# core.net
KiCad netlist of a schematic drawn in Altium Designer
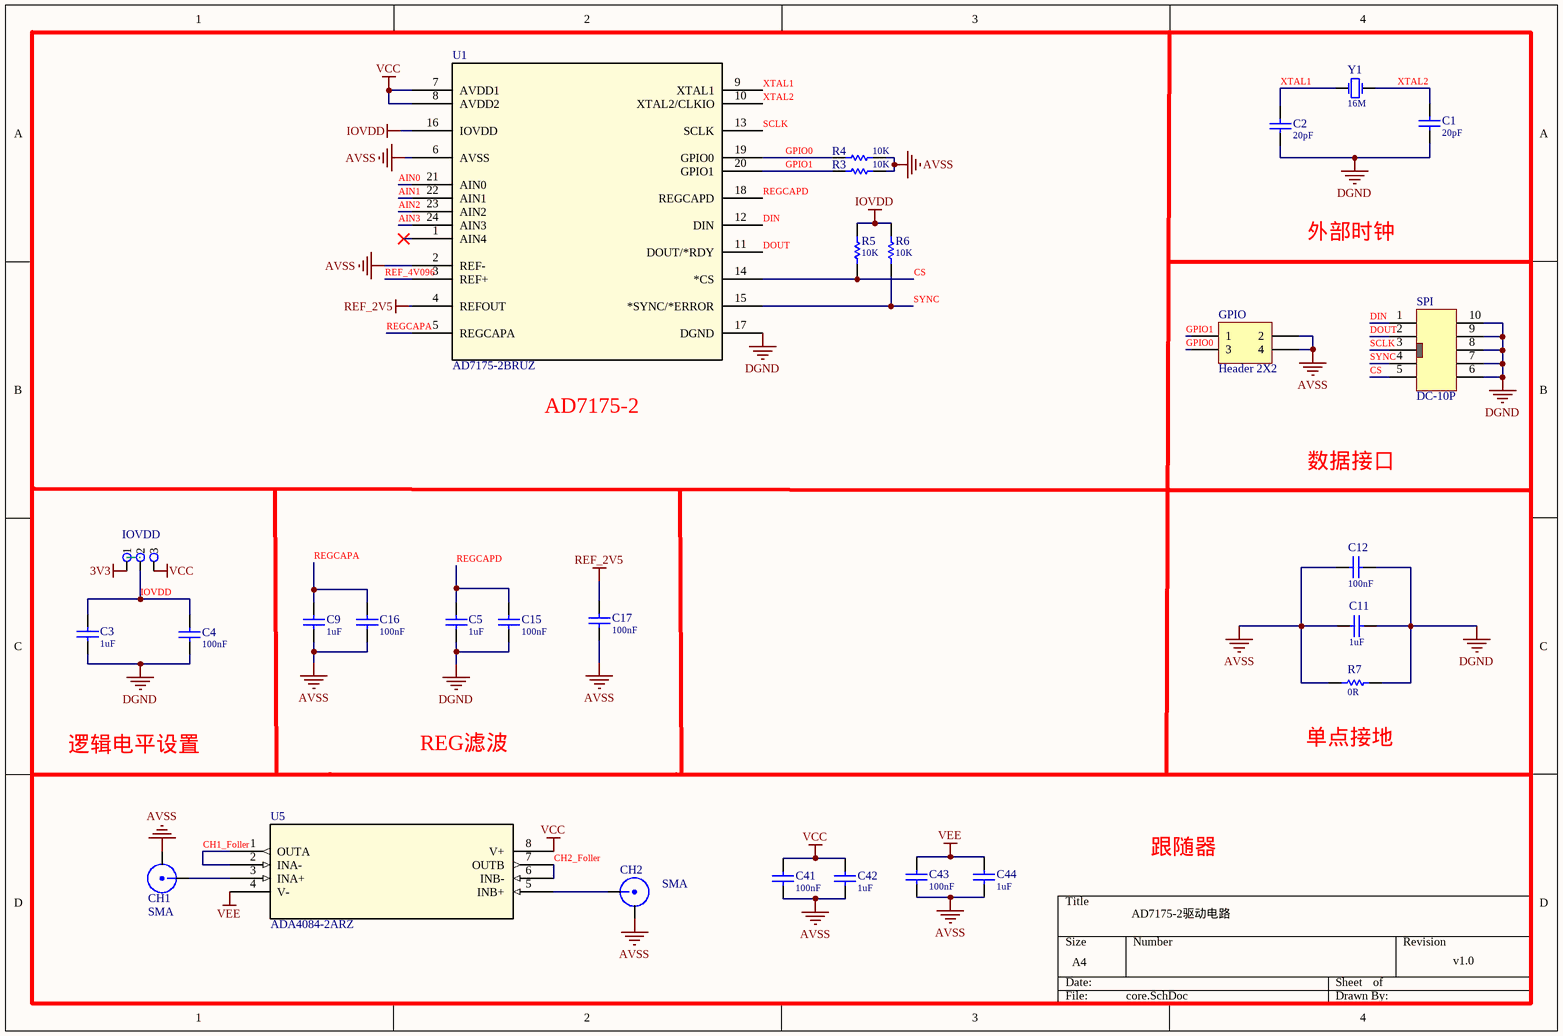
[diagram p0: core.SchDoc]

(export (version "E")
  (design (tool "Eeschema 10.0.6"))
  (components
    (comp (ref "C1")
      (value "20pF")
      (footprint "C0603-L")
      (description "贴片瓷片电容")
      (fields (field (name "Comment") "Cap-S"))
      (libsource (lib "XuZhe") (part "Cap-S"))
    )
    (comp (ref "C2")
      (value "20pF")
      (footprint "C0603-L")
      (description "贴片瓷片电容")
      (fields (field (name "Comment") "Cap-S"))
      (libsource (lib "XuZhe") (part "Cap-S"))
    )
    (comp (ref "C3")
      (value "1uF")
      (footprint "C0603-L")
      (description "贴片瓷片电容")
      (fields (field (name "Comment") "Cap-S"))
      (libsource (lib "XuZhe") (part "Cap-S"))
    )
    (comp (ref "C4")
      (value "100nF")
      (footprint "C0603-L")
      (description "贴片瓷片电容")
      (fields (field (name "Comment") "Cap-S"))
      (libsource (lib "XuZhe") (part "Cap-S"))
    )
    (comp (ref "C5")
      (value "1uF")
      (footprint "C0603-L")
      (description "贴片瓷片电容")
      (fields (field (name "Comment") "Cap-S"))
      (libsource (lib "XuZhe") (part "Cap-S"))
    )
    (comp (ref "C9")
      (value "1uF")
      (footprint "C0603-L")
      (description "贴片瓷片电容")
      (fields (field (name "Comment") "Cap-S"))
      (libsource (lib "XuZhe") (part "Cap-S"))
    )
    (comp (ref "C11")
      (value "1uF")
      (footprint "C0603-L")
      (description "贴片瓷片电容")
      (fields (field (name "Comment") "Cap-S"))
      (libsource (lib "XuZhe") (part "Cap-S"))
    )
    (comp (ref "C12")
      (value "100nF")
      (footprint "C0603-L")
      (description "贴片瓷片电容")
      (fields (field (name "Comment") "Cap-S"))
      (libsource (lib "XuZhe") (part "Cap-S"))
    )
    (comp (ref "C15")
      (value "100nF")
      (footprint "C0603-L")
      (description "贴片瓷片电容")
      (fields (field (name "Comment") "Cap-S"))
      (libsource (lib "XuZhe") (part "Cap-S"))
    )
    (comp (ref "C16")
      (value "100nF")
      (footprint "C0603-L")
      (description "贴片瓷片电容")
      (fields (field (name "Comment") "Cap-S"))
      (libsource (lib "XuZhe") (part "Cap-S"))
    )
    (comp (ref "C17")
      (value "100nF")
      (footprint "C0603-L")
      (description "贴片瓷片电容")
      (fields (field (name "Comment") "Cap-S"))
      (libsource (lib "XuZhe") (part "Cap-S"))
    )
    (comp (ref "C41")
      (value "100nF")
      (footprint "C0603-L")
      (description "贴片瓷片电容")
      (fields (field (name "Comment") "Cap-S"))
      (libsource (lib "XuZhe") (part "Cap-S"))
    )
    (comp (ref "C42")
      (value "1uF")
      (footprint "C0603-L")
      (description "贴片瓷片电容")
      (fields (field (name "Comment") "Cap-S"))
      (libsource (lib "XuZhe") (part "Cap-S"))
    )
    (comp (ref "C43")
      (value "100nF")
      (footprint "C0603-L")
      (description "贴片瓷片电容")
      (fields (field (name "Comment") "Cap-S"))
      (libsource (lib "XuZhe") (part "Cap-S"))
    )
    (comp (ref "C44")
      (value "1uF")
      (footprint "C0603-L")
      (description "贴片瓷片电容")
      (fields (field (name "Comment") "Cap-S"))
      (libsource (lib "XuZhe") (part "Cap-S"))
    )
    (comp (ref "CH1") (value "SMA") (footprint "SMA1") (libsource (lib "XuZhe") (part "SMA")))
    (comp (ref "CH2") (value "SMA") (footprint "SMA1") (libsource (lib "XuZhe") (part "SMA")))
    (comp (ref "GPIO")
      (value "Header 2X2")
      (footprint "HDR2X2")
      (description "Header, 2-Pin, Dual row")
      (fields (field (name "PUBLISHER") "Altium Limited"))
      (libsource (lib "Miscellaneous Connectors") (part "Header 2X2"))
    )
    (comp (ref "IOVDD") (value "Jumper") (footprint "JUMPER1x3") (libsource (lib "XuZhe") (part "Jumper1*3")))
    (comp (ref "R3")
      (value "10K")
      (footprint "R0603-L")
      (description "贴片电阻")
      (fields (field (name "Comment") "R"))
      (libsource (lib "XuZhe") (part "Res"))
    )
    (comp (ref "R4")
      (value "10K")
      (footprint "R0603-L")
      (description "贴片电阻")
      (fields (field (name "Comment") "R"))
      (libsource (lib "XuZhe") (part "Res"))
    )
    (comp (ref "R5")
      (value "10K")
      (footprint "R0603-L")
      (description "贴片电阻")
      (fields (field (name "Comment") "R"))
      (libsource (lib "XuZhe") (part "Res"))
    )
    (comp (ref "R6")
      (value "10K")
      (footprint "R0603-L")
      (description "贴片电阻")
      (fields (field (name "Comment") "R"))
      (libsource (lib "XuZhe") (part "Res"))
    )
    (comp (ref "R7")
      (value "0R")
      (footprint "R0603-L")
      (description "贴片电阻")
      (fields (field (name "Comment") "R"))
      (libsource (lib "XuZhe") (part "Res"))
    )
    (comp (ref "SPI") (value "DC-10P") (footprint "DC-10P") (libsource (lib "XuZhe") (part "DC-10P")))
    (comp (ref "U1")
      (value "AD7175-2BRUZ")
      (footprint "RU_24_ADI")
      (description "No Description Available")
      (fields (field (name "COPYRIGHT") "Copyright (C) 2021 Ultra Librarian. All rights reserved."))
      (libsource (lib "AD7175-2BRUZ") (part "AD7175-2BRUZ"))
    )
    (comp (ref "U5")
      (value "ADA4084-2ARZ")
      (footprint "R_8_ADI")
      (description "No Description Available")
      (fields (field (name "COPYRIGHT") "Copyright (C) 2021 Ultra Librarian. All rights reserved."))
      (libsource (lib "ADA4084-2ARZ") (part "ADA4084-2ARZ"))
    )
    (comp (ref "Y1")
      (value "16M")
      (footprint "XTAL-PB2-DIP")
      (description "晶振")
      (fields (field (name "Comment") "XTAL"))
      (libsource (lib "XuZhe") (part "XTAL"))
    )
  )
  (nets
    (net (code "1") (name "/AIN0") (class "Default")
      (node (ref "U1") (pin "21") (pinfunction "AIN0_21") (pintype "passive"))
    )
    (net (code "2") (name "/AIN1") (class "Default")
      (node (ref "U1") (pin "22") (pinfunction "AIN1_22") (pintype "passive"))
    )
    (net (code "3") (name "/AIN2") (class "Default")
      (node (ref "U1") (pin "23") (pinfunction "AIN2_23") (pintype "passive"))
    )
    (net (code "4") (name "/AIN3") (class "Default")
      (node (ref "U1") (pin "24") (pinfunction "AIN3_24") (pintype "passive"))
    )
    (net (code "5") (name "/CH1_Foller") (class "Default")
      (node (ref "U5") (pin "1") (pinfunction "OUTA_1") (pintype "output"))
      (node (ref "U5") (pin "2") (pinfunction "INA-_2") (pintype "input"))
    )
    (net (code "6") (name "/CH2_Foller") (class "Default")
      (node (ref "U5") (pin "6") (pinfunction "INB-_6") (pintype "input"))
      (node (ref "U5") (pin "7") (pinfunction "OUTB_7") (pintype "output"))
    )
    (net (code "7") (name "/CS") (class "Default")
      (node (ref "R5") (pin "1") (pinfunction "1_1") (pintype "passive"))
      (node (ref "SPI") (pin "5") (pinfunction "5_5") (pintype "passive"))
      (node (ref "U1") (pin "14") (pinfunction "*CS_14") (pintype "passive"))
    )
    (net (code "8") (name "/DIN") (class "Default")
      (node (ref "SPI") (pin "1") (pinfunction "1_1") (pintype "passive"))
      (node (ref "U1") (pin "12") (pinfunction "DIN_12") (pintype "passive"))
    )
    (net (code "9") (name "/DOUT") (class "Default")
      (node (ref "SPI") (pin "2") (pinfunction "2_2") (pintype "passive"))
      (node (ref "U1") (pin "11") (pinfunction "DOUT/*RDY_11") (pintype "passive"))
    )
    (net (code "10") (name "/GPIO0") (class "Default")
      (node (ref "GPIO") (pin "3") (pinfunction "3_3") (pintype "passive"))
      (node (ref "R4") (pin "2") (pinfunction "2_2") (pintype "passive"))
      (node (ref "U1") (pin "19") (pinfunction "GPIO0_19") (pintype "passive"))
    )
    (net (code "11") (name "/GPIO1") (class "Default")
      (node (ref "GPIO") (pin "1") (pinfunction "1_1") (pintype "passive"))
      (node (ref "R3") (pin "2") (pinfunction "2_2") (pintype "passive"))
      (node (ref "U1") (pin "20") (pinfunction "GPIO1_20") (pintype "passive"))
    )
    (net (code "12") (name "/REF_4V096") (class "Default")
      (node (ref "U1") (pin "3") (pinfunction "REF+_3") (pintype "passive"))
    )
    (net (code "13") (name "/REGCAPA") (class "Default")
      (node (ref "C16") (pin "2") (pinfunction "2_2") (pintype "passive"))
      (node (ref "C9") (pin "2") (pinfunction "2_2") (pintype "passive"))
      (node (ref "U1") (pin "5") (pinfunction "REGCAPA_5") (pintype "passive"))
    )
    (net (code "14") (name "/REGCAPD") (class "Default")
      (node (ref "C15") (pin "2") (pinfunction "2_2") (pintype "passive"))
      (node (ref "C5") (pin "2") (pinfunction "2_2") (pintype "passive"))
      (node (ref "U1") (pin "18") (pinfunction "REGCAPD_18") (pintype "passive"))
    )
    (net (code "15") (name "/SCLK") (class "Default")
      (node (ref "SPI") (pin "3") (pinfunction "3_3") (pintype "passive"))
      (node (ref "U1") (pin "13") (pinfunction "SCLK_13") (pintype "passive"))
    )
    (net (code "16") (name "/SYNC") (class "Default")
      (node (ref "R6") (pin "1") (pinfunction "1_1") (pintype "passive"))
      (node (ref "SPI") (pin "4") (pinfunction "4_4") (pintype "passive"))
      (node (ref "U1") (pin "15") (pinfunction "*SYNC/*ERROR_15") (pintype "passive"))
    )
    (net (code "17") (name "/XTAL1") (class "Default")
      (node (ref "C2") (pin "1") (pinfunction "1_1") (pintype "passive"))
      (node (ref "U1") (pin "9") (pinfunction "XTAL1_9") (pintype "passive"))
      (node (ref "Y1") (pin "1") (pinfunction "OSC1_1") (pintype "passive"))
    )
    (net (code "18") (name "/XTAL2") (class "Default")
      (node (ref "C1") (pin "1") (pinfunction "1_1") (pintype "passive"))
      (node (ref "U1") (pin "10") (pinfunction "XTAL2/CLKIO_10") (pintype "passive"))
      (node (ref "Y1") (pin "2") (pinfunction "OSC2_2") (pintype "passive"))
    )
    (net (code "19") (name "3V3") (class "Default")
      (node (ref "IOVDD") (pin "1") (pinfunction "1_1") (pintype "passive"))
    )
    (net (code "20") (name "AVSS") (class "Default")
      (node (ref "C11") (pin "2") (pinfunction "2_2") (pintype "passive"))
      (node (ref "C12") (pin "2") (pinfunction "2_2") (pintype "passive"))
      (node (ref "C16") (pin "1") (pinfunction "1_1") (pintype "passive"))
      (node (ref "C17") (pin "1") (pinfunction "1_1") (pintype "passive"))
      (node (ref "C41") (pin "1") (pinfunction "1_1") (pintype "passive"))
      (node (ref "C42") (pin "1") (pinfunction "1_1") (pintype "passive"))
      (node (ref "C43") (pin "1") (pinfunction "1_1") (pintype "passive"))
      (node (ref "C44") (pin "1") (pinfunction "1_1") (pintype "passive"))
      (node (ref "C9") (pin "1") (pinfunction "1_1") (pintype "passive"))
      (node (ref "CH1") (pin "2") (pinfunction "2_2") (pintype "passive"))
      (node (ref "CH2") (pin "2") (pinfunction "2_2") (pintype "passive"))
      (node (ref "GPIO") (pin "2") (pinfunction "2_2") (pintype "passive"))
      (node (ref "GPIO") (pin "4") (pinfunction "4_4") (pintype "passive"))
      (node (ref "R3") (pin "1") (pinfunction "1_1") (pintype "passive"))
      (node (ref "R4") (pin "1") (pinfunction "1_1") (pintype "passive"))
      (node (ref "R7") (pin "1") (pinfunction "1_1") (pintype "passive"))
      (node (ref "U1") (pin "2") (pinfunction "REF-_2") (pintype "passive"))
      (node (ref "U1") (pin "6") (pinfunction "AVSS_6") (pintype "passive"))
    )
    (net (code "21") (name "DGND") (class "Default")
      (node (ref "C1") (pin "2") (pinfunction "2_2") (pintype "passive"))
      (node (ref "C11") (pin "1") (pinfunction "1_1") (pintype "passive"))
      (node (ref "C12") (pin "1") (pinfunction "1_1") (pintype "passive"))
      (node (ref "C15") (pin "1") (pinfunction "1_1") (pintype "passive"))
      (node (ref "C2") (pin "2") (pinfunction "2_2") (pintype "passive"))
      (node (ref "C3") (pin "1") (pinfunction "1_1") (pintype "passive"))
      (node (ref "C4") (pin "1") (pinfunction "1_1") (pintype "passive"))
      (node (ref "C5") (pin "1") (pinfunction "1_1") (pintype "passive"))
      (node (ref "R7") (pin "2") (pinfunction "2_2") (pintype "passive"))
      (node (ref "SPI") (pin "10") (pinfunction "10_10") (pintype "passive"))
      (node (ref "SPI") (pin "6") (pinfunction "6_6") (pintype "passive"))
      (node (ref "SPI") (pin "7") (pinfunction "7_7") (pintype "passive"))
      (node (ref "SPI") (pin "8") (pinfunction "8_8") (pintype "passive"))
      (node (ref "SPI") (pin "9") (pinfunction "9_9") (pintype "passive"))
      (node (ref "U1") (pin "17") (pinfunction "DGND_17") (pintype "passive"))
    )
    (net (code "22") (name "IOVDD") (class "Default")
      (node (ref "C3") (pin "2") (pinfunction "2_2") (pintype "passive"))
      (node (ref "C4") (pin "2") (pinfunction "2_2") (pintype "passive"))
      (node (ref "IOVDD") (pin "2") (pinfunction "2_2") (pintype "passive"))
      (node (ref "R5") (pin "2") (pinfunction "2_2") (pintype "passive"))
      (node (ref "R6") (pin "2") (pinfunction "2_2") (pintype "passive"))
      (node (ref "U1") (pin "16") (pinfunction "IOVDD_16") (pintype "passive"))
    )
    (net (code "23") (name "Net-(U5-INA+)") (class "Default")
      (node (ref "CH1") (pin "1") (pinfunction "1_1") (pintype "passive"))
      (node (ref "U5") (pin "3") (pinfunction "INA+_3") (pintype "input"))
    )
    (net (code "24") (name "Net-(U5-INB+)") (class "Default")
      (node (ref "CH2") (pin "1") (pinfunction "1_1") (pintype "passive"))
      (node (ref "U5") (pin "5") (pinfunction "INB+_5") (pintype "input"))
    )
    (net (code "25") (name "REF_2V5") (class "Default")
      (node (ref "C17") (pin "2") (pinfunction "2_2") (pintype "passive"))
      (node (ref "U1") (pin "4") (pinfunction "REFOUT_4") (pintype "passive"))
    )
    (net (code "26") (name "VCC") (class "Default")
      (node (ref "C41") (pin "2") (pinfunction "2_2") (pintype "passive"))
      (node (ref "C42") (pin "2") (pinfunction "2_2") (pintype "passive"))
      (node (ref "IOVDD") (pin "3") (pinfunction "3_3") (pintype "passive"))
      (node (ref "U1") (pin "7") (pinfunction "AVDD1_7") (pintype "passive"))
      (node (ref "U1") (pin "8") (pinfunction "AVDD2_8") (pintype "passive"))
      (node (ref "U5") (pin "8") (pinfunction "V+_8") (pintype "power_in"))
    )
    (net (code "27") (name "VEE") (class "Default")
      (node (ref "C43") (pin "2") (pinfunction "2_2") (pintype "passive"))
      (node (ref "C44") (pin "2") (pinfunction "2_2") (pintype "passive"))
      (node (ref "U5") (pin "4") (pinfunction "V-_4") (pintype "power_in"))
    )
    (net (code "28") (name "unconnected-(U1-AIN4-Pad1)") (class "Default")
      (node (ref "U1") (pin "1") (pinfunction "AIN4_1") (pintype "passive+no_connect"))
    )
  )
)
